# TPLE.net
KiCad netlist of a schematic drawn in EAGLE
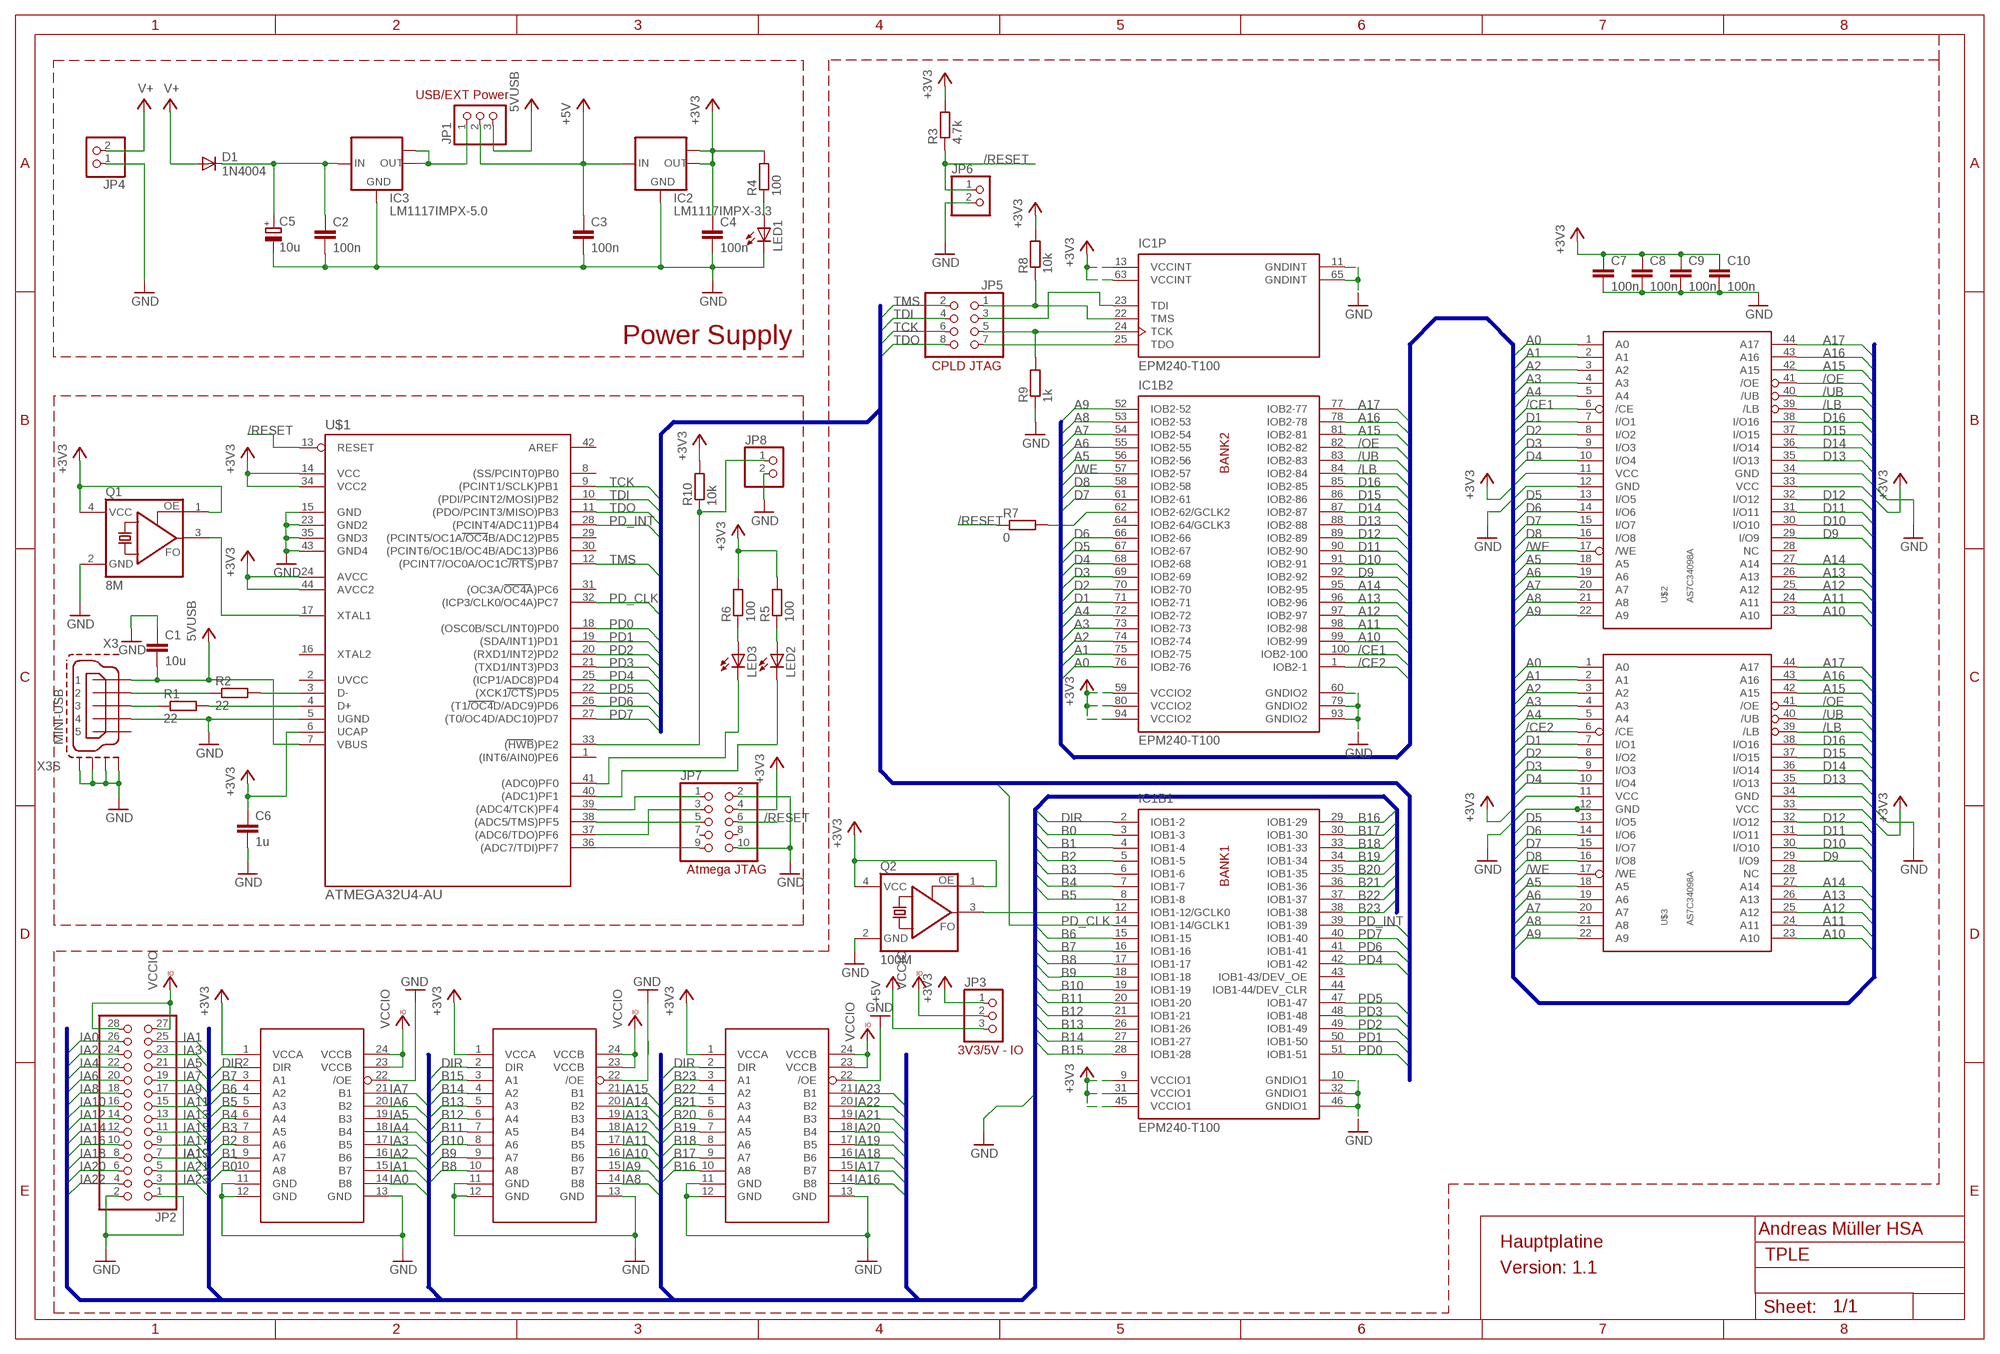
[diagram p0: schematic, sheet 1]

(export (version "E")
  (design (tool "Eeschema 10.0.6"))
  (components
    (comp (ref "C1")
      (value "10u")
      (footprint "eagle-import:C3216")
      (libsource (lib "eagle-import") (part "C-EUC3216"))
    )
    (comp (ref "C2")
      (value "100n")
      (footprint "eagle-import:C1206")
      (libsource (lib "eagle-import") (part "C-EUC1206"))
    )
    (comp (ref "C3")
      (value "100n")
      (footprint "eagle-import:C1206")
      (libsource (lib "eagle-import") (part "C-EUC1206"))
    )
    (comp (ref "C4")
      (value "100n")
      (footprint "eagle-import:C1206")
      (libsource (lib "eagle-import") (part "C-EUC1206"))
    )
    (comp (ref "C5")
      (value "10u")
      (footprint "eagle-import:E2-5")
      (libsource (lib "eagle-import") (part "CPOL-EUE2-5"))
    )
    (comp (ref "C6")
      (value "1u")
      (footprint "eagle-import:C0402")
      (libsource (lib "eagle-import") (part "C-EUC0402"))
    )
    (comp (ref "C7")
      (value "100n")
      (footprint "eagle-import:C0402")
      (libsource (lib "eagle-import") (part "C-EUC0402"))
    )
    (comp (ref "C8")
      (value "100n")
      (footprint "eagle-import:C0402")
      (libsource (lib "eagle-import") (part "C-EUC0402"))
    )
    (comp (ref "C9")
      (value "100n")
      (footprint "eagle-import:C0402")
      (libsource (lib "eagle-import") (part "C-EUC0402"))
    )
    (comp (ref "C10")
      (value "100n")
      (footprint "eagle-import:C0402")
      (libsource (lib "eagle-import") (part "C-EUC0402"))
    )
    (comp (ref "D1")
      (value "1N4004")
      (footprint "eagle-import:DO41-10")
      (libsource (lib "eagle-import") (part "1N4004"))
    )
    (comp (ref "IC1")
      (value "EPM240-T100")
      (footprint "eagle-import:TQFP100")
      (libsource (lib "eagle-import") (part "EPM240-T100"))
    )
    (comp (ref "IC2")
      (value "LM1117IMPX-3.3")
      (footprint "eagle-import:SOT223")
      (libsource (lib "eagle-import") (part "LM1117IMPX-3.3"))
    )
    (comp (ref "IC3")
      (value "LM1117IMPX-5.0")
      (footprint "eagle-import:SOT223")
      (libsource (lib "eagle-import") (part "LM1117IMPX-5.0"))
    )
    (comp (ref "JP1")
      (value "PINHD-1X3")
      (footprint "eagle-import:1X03")
      (libsource (lib "eagle-import") (part "PINHD-1X3"))
    )
    (comp (ref "JP2")
      (value "PINHD-2X14")
      (footprint "eagle-import:2X14")
      (libsource (lib "eagle-import") (part "PINHD-2X14"))
    )
    (comp (ref "JP3")
      (value "PINHD-1X3")
      (footprint "eagle-import:1X03")
      (libsource (lib "eagle-import") (part "PINHD-1X3"))
    )
    (comp (ref "JP4")
      (value "PINHD-1X2")
      (footprint "eagle-import:1X02")
      (libsource (lib "eagle-import") (part "PINHD-1X2"))
    )
    (comp (ref "JP5")
      (value "PINHD-2X4")
      (footprint "eagle-import:2X04")
      (libsource (lib "eagle-import") (part "PINHD-2X4"))
    )
    (comp (ref "JP6")
      (value "PINHD-1X2")
      (footprint "eagle-import:1X02")
      (libsource (lib "eagle-import") (part "PINHD-1X2"))
    )
    (comp (ref "JP7")
      (value "PINHD-2X5")
      (footprint "eagle-import:2X05")
      (libsource (lib "eagle-import") (part "PINHD-2X5"))
    )
    (comp (ref "JP8")
      (value "PINHD-1X2")
      (footprint "eagle-import:1X02")
      (libsource (lib "eagle-import") (part "PINHD-1X2"))
    )
    (comp (ref "LED1")
      (value "LEDSMT1206")
      (footprint "eagle-import:1206")
      (libsource (lib "eagle-import") (part "LEDSMT1206"))
    )
    (comp (ref "LED2")
      (value "LEDSMT1206")
      (footprint "eagle-import:1206")
      (libsource (lib "eagle-import") (part "LEDSMT1206"))
    )
    (comp (ref "LED3")
      (value "LEDSMT1206")
      (footprint "eagle-import:1206")
      (libsource (lib "eagle-import") (part "LEDSMT1206"))
    )
    (comp (ref "Q1")
      (value "8M")
      (footprint "eagle-import:ASF")
      (libsource (lib "eagle-import") (part "ASFL1"))
    )
    (comp (ref "Q2")
      (value "100M")
      (footprint "eagle-import:ASF")
      (libsource (lib "eagle-import") (part "ASFL1"))
    )
    (comp (ref "R1")
      (value "22")
      (footprint "eagle-import:M3216")
      (libsource (lib "eagle-import") (part "resistor_R-EU_M3216"))
    )
    (comp (ref "R2")
      (value "22")
      (footprint "eagle-import:M3216")
      (libsource (lib "eagle-import") (part "resistor_R-EU_M3216"))
    )
    (comp (ref "R3")
      (value "4.7k")
      (footprint "eagle-import:M3216")
      (libsource (lib "eagle-import") (part "resistor_R-EU_M3216"))
    )
    (comp (ref "R4")
      (value "100")
      (footprint "eagle-import:M3216")
      (libsource (lib "eagle-import") (part "resistor_R-EU_M3216"))
    )
    (comp (ref "R5")
      (value "100")
      (footprint "eagle-import:M3216")
      (libsource (lib "eagle-import") (part "resistor_R-EU_M3216"))
    )
    (comp (ref "R6")
      (value "100")
      (footprint "eagle-import:M3216")
      (libsource (lib "eagle-import") (part "resistor_R-EU_M3216"))
    )
    (comp (ref "R7")
      (value "0")
      (footprint "eagle-import:R0201")
      (libsource (lib "eagle-import") (part "R-EU_R0201"))
    )
    (comp (ref "R8")
      (value "10k")
      (footprint "eagle-import:M3216")
      (libsource (lib "eagle-import") (part "resistor_R-EU_M3216"))
    )
    (comp (ref "R9")
      (value "1k")
      (footprint "eagle-import:M3216")
      (libsource (lib "eagle-import") (part "resistor_R-EU_M3216"))
    )
    (comp (ref "R10")
      (value "10k")
      (footprint "eagle-import:R0402")
      (libsource (lib "eagle-import") (part "R-EU_R0402"))
    )
    (comp (ref "U$1")
      (value "ATMEGA32U4-AU")
      (footprint "eagle-import:TQFP44")
      (libsource (lib "eagle-import") (part "ATMEGA32U4-AU"))
    )
    (comp (ref "U$2")
      (value "AS7C34098A")
      (footprint "eagle-import:TSOP44-T2")
      (libsource (lib "eagle-import") (part "AS7C34098A"))
    )
    (comp (ref "U$3")
      (value "AS7C34098A")
      (footprint "eagle-import:TSOP44-T2")
      (libsource (lib "eagle-import") (part "AS7C34098A"))
    )
    (comp (ref "U$4")
      (value "SN74LVC8T245")
      (footprint "eagle-import:TVSOP24")
      (libsource (lib "eagle-import") (part "SN74LVC8T245"))
    )
    (comp (ref "U$5")
      (value "SN74LVC8T245")
      (footprint "eagle-import:TVSOP24")
      (libsource (lib "eagle-import") (part "SN74LVC8T245"))
    )
    (comp (ref "U$6")
      (value "SN74LVC8T245")
      (footprint "eagle-import:TVSOP24")
      (libsource (lib "eagle-import") (part "SN74LVC8T245"))
    )
    (comp (ref "X3")
      (value "MINI-USB")
      (footprint "eagle-import:UX60A-MB-5ST")
      (libsource (lib "eagle-import") (part "MINI-USB-SHIELD-UX60A-MB-5ST"))
    )
  )
  (nets
    (net (code "1") (name "+3V3") (class "Default")
      (node (ref "C10") (pin "1") (pinfunction "1_1") (pintype "passive"))
      (node (ref "C4") (pin "1") (pinfunction "1_1") (pintype "passive"))
      (node (ref "C6") (pin "1") (pinfunction "1_1") (pintype "passive"))
      (node (ref "C7") (pin "1") (pinfunction "1_1") (pintype "passive"))
      (node (ref "C8") (pin "1") (pinfunction "1_1") (pintype "passive"))
      (node (ref "C9") (pin "1") (pinfunction "1_1") (pintype "passive"))
      (node (ref "IC1") (pin "13") (pinfunction "VCCINT_13") (pintype "power_in"))
      (node (ref "IC1") (pin "31") (pinfunction "VCCIO1_31") (pintype "power_in"))
      (node (ref "IC1") (pin "45") (pinfunction "VCCIO1_45") (pintype "power_in"))
      (node (ref "IC1") (pin "59") (pinfunction "VCCIO2_59") (pintype "power_in"))
      (node (ref "IC1") (pin "63") (pinfunction "VCCINT_63") (pintype "power_in"))
      (node (ref "IC1") (pin "80") (pinfunction "VCCIO2_80") (pintype "power_in"))
      (node (ref "IC1") (pin "9") (pinfunction "VCCIO1_9") (pintype "power_in"))
      (node (ref "IC1") (pin "94") (pinfunction "VCCIO2_94") (pintype "power_in"))
      (node (ref "IC2") (pin "2") (pinfunction "OUT_2") (pintype "passive"))
      (node (ref "IC2") (pin "TAB") (pinfunction "OUT1_TAB") (pintype "passive"))
      (node (ref "JP3") (pin "1") (pinfunction "1_1") (pintype "passive"))
      (node (ref "JP7") (pin "4") (pinfunction "4_4") (pintype "passive"))
      (node (ref "Q1") (pin "1") (pinfunction "OE_1") (pintype "input"))
      (node (ref "Q1") (pin "4") (pinfunction "VCC_4") (pintype "power_in"))
      (node (ref "Q2") (pin "1") (pinfunction "OE_1") (pintype "input"))
      (node (ref "Q2") (pin "4") (pinfunction "VCC_4") (pintype "power_in"))
      (node (ref "R10") (pin "2") (pinfunction "2_2") (pintype "passive"))
      (node (ref "R3") (pin "2") (pinfunction "2_2") (pintype "passive"))
      (node (ref "R4") (pin "2") (pinfunction "2_2") (pintype "passive"))
      (node (ref "R5") (pin "2") (pinfunction "2_2") (pintype "passive"))
      (node (ref "R6") (pin "2") (pinfunction "2_2") (pintype "passive"))
      (node (ref "R8") (pin "2") (pinfunction "2_2") (pintype "passive"))
      (node (ref "U$1") (pin "14") (pinfunction "VCC_14") (pintype "bidirectional"))
      (node (ref "U$1") (pin "24") (pinfunction "AVCC_24") (pintype "bidirectional"))
      (node (ref "U$1") (pin "34") (pinfunction "VCC2_34") (pintype "bidirectional"))
      (node (ref "U$1") (pin "44") (pinfunction "AVCC2_44") (pintype "bidirectional"))
      (node (ref "U$1") (pin "6") (pinfunction "UCAP_6") (pintype "bidirectional"))
      (node (ref "U$2") (pin "11") (pinfunction "VCC_11") (pintype "power_in"))
      (node (ref "U$2") (pin "33") (pinfunction "VCC_33") (pintype "power_in"))
      (node (ref "U$3") (pin "11") (pinfunction "VCC_11") (pintype "power_in"))
      (node (ref "U$3") (pin "33") (pinfunction "VCC_33") (pintype "power_in"))
      (node (ref "U$4") (pin "1") (pinfunction "VCCA_1") (pintype "power_in"))
      (node (ref "U$5") (pin "1") (pinfunction "VCCA_1") (pintype "power_in"))
      (node (ref "U$6") (pin "1") (pinfunction "VCCA_1") (pintype "power_in"))
    )
    (net (code "2") (name "+5V") (class "Default")
      (node (ref "C3") (pin "1") (pinfunction "1_1") (pintype "passive"))
      (node (ref "IC2") (pin "3") (pinfunction "IN_3") (pintype "input"))
      (node (ref "JP1") (pin "2") (pinfunction "2_2") (pintype "passive"))
      (node (ref "JP3") (pin "3") (pinfunction "3_3") (pintype "passive"))
    )
    (net (code "3") (name "/A0") (class "Default")
      (node (ref "IC1") (pin "76") (pinfunction "IOB2-76_76") (pintype "bidirectional"))
      (node (ref "U$2") (pin "1") (pinfunction "A0_1") (pintype "input"))
      (node (ref "U$3") (pin "1") (pinfunction "A0_1") (pintype "input"))
    )
    (net (code "4") (name "/A1") (class "Default")
      (node (ref "IC1") (pin "75") (pinfunction "IOB2-75_75") (pintype "bidirectional"))
      (node (ref "U$2") (pin "2") (pinfunction "A1_2") (pintype "input"))
      (node (ref "U$3") (pin "2") (pinfunction "A1_2") (pintype "input"))
    )
    (net (code "5") (name "/A2") (class "Default")
      (node (ref "IC1") (pin "74") (pinfunction "IOB2-74_74") (pintype "bidirectional"))
      (node (ref "U$2") (pin "3") (pinfunction "A2_3") (pintype "input"))
      (node (ref "U$3") (pin "3") (pinfunction "A2_3") (pintype "input"))
    )
    (net (code "6") (name "/A3") (class "Default")
      (node (ref "IC1") (pin "73") (pinfunction "IOB2-73_73") (pintype "bidirectional"))
      (node (ref "U$2") (pin "4") (pinfunction "A3_4") (pintype "input"))
      (node (ref "U$3") (pin "4") (pinfunction "A3_4") (pintype "input"))
    )
    (net (code "7") (name "/A4") (class "Default")
      (node (ref "IC1") (pin "72") (pinfunction "IOB2-72_72") (pintype "bidirectional"))
      (node (ref "U$2") (pin "5") (pinfunction "A4_5") (pintype "input"))
      (node (ref "U$3") (pin "5") (pinfunction "A4_5") (pintype "input"))
    )
    (net (code "8") (name "/A5") (class "Default")
      (node (ref "IC1") (pin "56") (pinfunction "IOB2-56_56") (pintype "bidirectional"))
      (node (ref "U$2") (pin "18") (pinfunction "A5_18") (pintype "input"))
      (node (ref "U$3") (pin "18") (pinfunction "A5_18") (pintype "input"))
    )
    (net (code "9") (name "/A6") (class "Default")
      (node (ref "IC1") (pin "55") (pinfunction "IOB2-55_55") (pintype "bidirectional"))
      (node (ref "U$2") (pin "19") (pinfunction "A6_19") (pintype "input"))
      (node (ref "U$3") (pin "19") (pinfunction "A6_19") (pintype "input"))
    )
    (net (code "10") (name "/A7") (class "Default")
      (node (ref "IC1") (pin "54") (pinfunction "IOB2-54_54") (pintype "bidirectional"))
      (node (ref "U$2") (pin "20") (pinfunction "A7_20") (pintype "input"))
      (node (ref "U$3") (pin "20") (pinfunction "A7_20") (pintype "input"))
    )
    (net (code "11") (name "/A8") (class "Default")
      (node (ref "IC1") (pin "53") (pinfunction "IOB2-53_53") (pintype "bidirectional"))
      (node (ref "U$2") (pin "21") (pinfunction "A8_21") (pintype "input"))
      (node (ref "U$3") (pin "21") (pinfunction "A8_21") (pintype "input"))
    )
    (net (code "12") (name "/A9") (class "Default")
      (node (ref "IC1") (pin "52") (pinfunction "IOB2-52_52") (pintype "bidirectional"))
      (node (ref "U$2") (pin "22") (pinfunction "A9_22") (pintype "input"))
      (node (ref "U$3") (pin "22") (pinfunction "A9_22") (pintype "input"))
    )
    (net (code "13") (name "/A10") (class "Default")
      (node (ref "IC1") (pin "99") (pinfunction "IOB2-99_99") (pintype "bidirectional"))
      (node (ref "U$2") (pin "23") (pinfunction "A10_23") (pintype "input"))
      (node (ref "U$3") (pin "23") (pinfunction "A10_23") (pintype "input"))
    )
    (net (code "14") (name "/A11") (class "Default")
      (node (ref "IC1") (pin "98") (pinfunction "IOB2-98_98") (pintype "bidirectional"))
      (node (ref "U$2") (pin "24") (pinfunction "A11_24") (pintype "input"))
      (node (ref "U$3") (pin "24") (pinfunction "A11_24") (pintype "input"))
    )
    (net (code "15") (name "/A12") (class "Default")
      (node (ref "IC1") (pin "97") (pinfunction "IOB2-97_97") (pintype "bidirectional"))
      (node (ref "U$2") (pin "25") (pinfunction "A12_25") (pintype "input"))
      (node (ref "U$3") (pin "25") (pinfunction "A12_25") (pintype "input"))
    )
    (net (code "16") (name "/A13") (class "Default")
      (node (ref "IC1") (pin "96") (pinfunction "IOB2-96_96") (pintype "bidirectional"))
      (node (ref "U$2") (pin "26") (pinfunction "A13_26") (pintype "input"))
      (node (ref "U$3") (pin "26") (pinfunction "A13_26") (pintype "input"))
    )
    (net (code "17") (name "/A14") (class "Default")
      (node (ref "IC1") (pin "95") (pinfunction "IOB2-95_95") (pintype "bidirectional"))
      (node (ref "U$2") (pin "27") (pinfunction "A14_27") (pintype "input"))
      (node (ref "U$3") (pin "27") (pinfunction "A14_27") (pintype "input"))
    )
    (net (code "18") (name "/A15") (class "Default")
      (node (ref "IC1") (pin "81") (pinfunction "IOB2-81_81") (pintype "bidirectional"))
      (node (ref "U$2") (pin "42") (pinfunction "A15_42") (pintype "input"))
      (node (ref "U$3") (pin "42") (pinfunction "A15_42") (pintype "input"))
    )
    (net (code "19") (name "/A16") (class "Default")
      (node (ref "IC1") (pin "78") (pinfunction "IOB2-78_78") (pintype "bidirectional"))
      (node (ref "U$2") (pin "43") (pinfunction "A16_43") (pintype "input"))
      (node (ref "U$3") (pin "43") (pinfunction "A16_43") (pintype "input"))
    )
    (net (code "20") (name "/A17") (class "Default")
      (node (ref "IC1") (pin "77") (pinfunction "IOB2-77_77") (pintype "bidirectional"))
      (node (ref "U$2") (pin "44") (pinfunction "A17_44") (pintype "input"))
      (node (ref "U$3") (pin "44") (pinfunction "A17_44") (pintype "input"))
    )
    (net (code "21") (name "/B0") (class "Default")
      (node (ref "IC1") (pin "3") (pinfunction "IOB1-3_3") (pintype "bidirectional"))
      (node (ref "U$4") (pin "10") (pinfunction "A8_10") (pintype "bidirectional"))
    )
    (net (code "22") (name "/B1") (class "Default")
      (node (ref "IC1") (pin "4") (pinfunction "IOB1-4_4") (pintype "bidirectional"))
      (node (ref "U$4") (pin "9") (pinfunction "A7_9") (pintype "bidirectional"))
    )
    (net (code "23") (name "/B2") (class "Default")
      (node (ref "IC1") (pin "5") (pinfunction "IOB1-5_5") (pintype "bidirectional"))
      (node (ref "U$4") (pin "8") (pinfunction "A6_8") (pintype "bidirectional"))
    )
    (net (code "24") (name "/B3") (class "Default")
      (node (ref "IC1") (pin "6") (pinfunction "IOB1-6_6") (pintype "bidirectional"))
      (node (ref "U$4") (pin "7") (pinfunction "A5_7") (pintype "bidirectional"))
    )
    (net (code "25") (name "/B4") (class "Default")
      (node (ref "IC1") (pin "7") (pinfunction "IOB1-7_7") (pintype "bidirectional"))
      (node (ref "U$4") (pin "6") (pinfunction "A4_6") (pintype "bidirectional"))
    )
    (net (code "26") (name "/B5") (class "Default")
      (node (ref "IC1") (pin "8") (pinfunction "IOB1-8_8") (pintype "bidirectional"))
      (node (ref "U$4") (pin "5") (pinfunction "A3_5") (pintype "bidirectional"))
    )
    (net (code "27") (name "/B6") (class "Default")
      (node (ref "IC1") (pin "15") (pinfunction "IOB1-15_15") (pintype "bidirectional"))
      (node (ref "U$4") (pin "4") (pinfunction "A2_4") (pintype "bidirectional"))
    )
    (net (code "28") (name "/B7") (class "Default")
      (node (ref "IC1") (pin "16") (pinfunction "IOB1-16_16") (pintype "bidirectional"))
      (node (ref "U$4") (pin "3") (pinfunction "A1_3") (pintype "bidirectional"))
    )
    (net (code "29") (name "/B8") (class "Default")
      (node (ref "IC1") (pin "17") (pinfunction "IOB1-17_17") (pintype "bidirectional"))
      (node (ref "U$5") (pin "10") (pinfunction "A8_10") (pintype "bidirectional"))
    )
    (net (code "30") (name "/B9") (class "Default")
      (node (ref "IC1") (pin "18") (pinfunction "IOB1-18_18") (pintype "bidirectional"))
      (node (ref "U$5") (pin "9") (pinfunction "A7_9") (pintype "bidirectional"))
    )
    (net (code "31") (name "/B10") (class "Default")
      (node (ref "IC1") (pin "19") (pinfunction "IOB1-19_19") (pintype "bidirectional"))
      (node (ref "U$5") (pin "8") (pinfunction "A6_8") (pintype "bidirectional"))
    )
    (net (code "32") (name "/B11") (class "Default")
      (node (ref "IC1") (pin "20") (pinfunction "IOB1-20_20") (pintype "bidirectional"))
      (node (ref "U$5") (pin "7") (pinfunction "A5_7") (pintype "bidirectional"))
    )
    (net (code "33") (name "/B12") (class "Default")
      (node (ref "IC1") (pin "21") (pinfunction "IOB1-21_21") (pintype "bidirectional"))
      (node (ref "U$5") (pin "6") (pinfunction "A4_6") (pintype "bidirectional"))
    )
    (net (code "34") (name "/B13") (class "Default")
      (node (ref "IC1") (pin "26") (pinfunction "IOB1-26_26") (pintype "bidirectional"))
      (node (ref "U$5") (pin "5") (pinfunction "A3_5") (pintype "bidirectional"))
    )
    (net (code "35") (name "/B14") (class "Default")
      (node (ref "IC1") (pin "27") (pinfunction "IOB1-27_27") (pintype "bidirectional"))
      (node (ref "U$5") (pin "4") (pinfunction "A2_4") (pintype "bidirectional"))
    )
    (net (code "36") (name "/B15") (class "Default")
      (node (ref "IC1") (pin "28") (pinfunction "IOB1-28_28") (pintype "bidirectional"))
      (node (ref "U$5") (pin "3") (pinfunction "A1_3") (pintype "bidirectional"))
    )
    (net (code "37") (name "/B16") (class "Default")
      (node (ref "IC1") (pin "29") (pinfunction "IOB1-29_29") (pintype "bidirectional"))
      (node (ref "U$6") (pin "10") (pinfunction "A8_10") (pintype "bidirectional"))
    )
    (net (code "38") (name "/B17") (class "Default")
      (node (ref "IC1") (pin "30") (pinfunction "IOB1-30_30") (pintype "bidirectional"))
      (node (ref "U$6") (pin "9") (pinfunction "A7_9") (pintype "bidirectional"))
    )
    (net (code "39") (name "/B18") (class "Default")
      (node (ref "IC1") (pin "33") (pinfunction "IOB1-33_33") (pintype "bidirectional"))
      (node (ref "U$6") (pin "8") (pinfunction "A6_8") (pintype "bidirectional"))
    )
    (net (code "40") (name "/B19") (class "Default")
      (node (ref "IC1") (pin "34") (pinfunction "IOB1-34_34") (pintype "bidirectional"))
      (node (ref "U$6") (pin "7") (pinfunction "A5_7") (pintype "bidirectional"))
    )
    (net (code "41") (name "/B20") (class "Default")
      (node (ref "IC1") (pin "35") (pinfunction "IOB1-35_35") (pintype "bidirectional"))
      (node (ref "U$6") (pin "6") (pinfunction "A4_6") (pintype "bidirectional"))
    )
    (net (code "42") (name "/B21") (class "Default")
      (node (ref "IC1") (pin "36") (pinfunction "IOB1-36_36") (pintype "bidirectional"))
      (node (ref "U$6") (pin "5") (pinfunction "A3_5") (pintype "bidirectional"))
    )
    (net (code "43") (name "/B22") (class "Default")
      (node (ref "IC1") (pin "37") (pinfunction "IOB1-37_37") (pintype "bidirectional"))
      (node (ref "U$6") (pin "4") (pinfunction "A2_4") (pintype "bidirectional"))
    )
    (net (code "44") (name "/B23") (class "Default")
      (node (ref "IC1") (pin "38") (pinfunction "IOB1-38_38") (pintype "bidirectional"))
      (node (ref "U$6") (pin "3") (pinfunction "A1_3") (pintype "bidirectional"))
    )
    (net (code "45") (name "/D1") (class "Default")
      (node (ref "IC1") (pin "71") (pinfunction "IOB2-71_71") (pintype "bidirectional"))
      (node (ref "U$2") (pin "7") (pinfunction "I/O1_7") (pintype "bidirectional"))
      (node (ref "U$3") (pin "7") (pinfunction "I/O1_7") (pintype "bidirectional"))
    )
    (net (code "46") (name "/D2") (class "Default")
      (node (ref "IC1") (pin "70") (pinfunction "IOB2-70_70") (pintype "bidirectional"))
      (node (ref "U$2") (pin "8") (pinfunction "I/O2_8") (pintype "bidirectional"))
      (node (ref "U$3") (pin "8") (pinfunction "I/O2_8") (pintype "bidirectional"))
    )
    (net (code "47") (name "/D3") (class "Default")
      (node (ref "IC1") (pin "69") (pinfunction "IOB2-69_69") (pintype "bidirectional"))
      (node (ref "U$2") (pin "9") (pinfunction "I/O3_9") (pintype "bidirectional"))
      (node (ref "U$3") (pin "9") (pinfunction "I/O3_9") (pintype "bidirectional"))
    )
    (net (code "48") (name "/D4") (class "Default")
      (node (ref "IC1") (pin "68") (pinfunction "IOB2-68_68") (pintype "bidirectional"))
      (node (ref "U$2") (pin "10") (pinfunction "I/O4_10") (pintype "bidirectional"))
      (node (ref "U$3") (pin "10") (pinfunction "I/O4_10") (pintype "bidirectional"))
    )
    (net (code "49") (name "/D5") (class "Default")
      (node (ref "IC1") (pin "67") (pinfunction "IOB2-67_67") (pintype "bidirectional"))
      (node (ref "U$2") (pin "13") (pinfunction "I/O5_13") (pintype "bidirectional"))
      (node (ref "U$3") (pin "13") (pinfunction "I/O5_13") (pintype "bidirectional"))
    )
    (net (code "50") (name "/D6") (class "Default")
      (node (ref "IC1") (pin "66") (pinfunction "IOB2-66_66") (pintype "bidirectional"))
      (node (ref "U$2") (pin "14") (pinfunction "I/O6_14") (pintype "bidirectional"))
      (node (ref "U$3") (pin "14") (pinfunction "I/O6_14") (pintype "bidirectional"))
    )
    (net (code "51") (name "/D7") (class "Default")
      (node (ref "IC1") (pin "61") (pinfunction "IOB2-61_61") (pintype "bidirectional"))
      (node (ref "U$2") (pin "15") (pinfunction "I/O7_15") (pintype "bidirectional"))
      (node (ref "U$3") (pin "15") (pinfunction "I/O7_15") (pintype "bidirectional"))
    )
    (net (code "52") (name "/D8") (class "Default")
      (node (ref "IC1") (pin "58") (pinfunction "IOB2-58_58") (pintype "bidirectional"))
      (node (ref "U$2") (pin "16") (pinfunction "I/O8_16") (pintype "bidirectional"))
      (node (ref "U$3") (pin "16") (pinfunction "I/O8_16") (pintype "bidirectional"))
    )
    (net (code "53") (name "/D9") (class "Default")
      (node (ref "IC1") (pin "92") (pinfunction "IOB2-92_92") (pintype "bidirectional"))
      (node (ref "U$2") (pin "29") (pinfunction "I/O9_29") (pintype "bidirectional"))
      (node (ref "U$3") (pin "29") (pinfunction "I/O9_29") (pintype "bidirectional"))
    )
    (net (code "54") (name "/D10") (class "Default")
      (node (ref "IC1") (pin "91") (pinfunction "IOB2-91_91") (pintype "bidirectional"))
      (node (ref "U$2") (pin "30") (pinfunction "I/O10_30") (pintype "bidirectional"))
      (node (ref "U$3") (pin "30") (pinfunction "I/O10_30") (pintype "bidirectional"))
    )
    (net (code "55") (name "/D11") (class "Default")
      (node (ref "IC1") (pin "90") (pinfunction "IOB2-90_90") (pintype "bidirectional"))
      (node (ref "U$2") (pin "31") (pinfunction "I/O11_31") (pintype "bidirectional"))
      (node (ref "U$3") (pin "31") (pinfunction "I/O11_31") (pintype "bidirectional"))
    )
    (net (code "56") (name "/D12") (class "Default")
      (node (ref "IC1") (pin "89") (pinfunction "IOB2-89_89") (pintype "bidirectional"))
      (node (ref "U$2") (pin "32") (pinfunction "I/O12_32") (pintype "bidirectional"))
      (node (ref "U$3") (pin "32") (pinfunction "I/O12_32") (pintype "bidirectional"))
    )
    (net (code "57") (name "/D13") (class "Default")
      (node (ref "IC1") (pin "88") (pinfunction "IOB2-88_88") (pintype "bidirectional"))
      (node (ref "U$2") (pin "35") (pinfunction "I/O13_35") (pintype "bidirectional"))
      (node (ref "U$3") (pin "35") (pinfunction "I/O13_35") (pintype "bidirectional"))
    )
    (net (code "58") (name "/D14") (class "Default")
      (node (ref "IC1") (pin "87") (pinfunction "IOB2-87_87") (pintype "bidirectional"))
      (node (ref "U$2") (pin "36") (pinfunction "I/O14_36") (pintype "bidirectional"))
      (node (ref "U$3") (pin "36") (pinfunction "I/O14_36") (pintype "bidirectional"))
    )
    (net (code "59") (name "/D15") (class "Default")
      (node (ref "IC1") (pin "86") (pinfunction "IOB2-86_86") (pintype "bidirectional"))
      (node (ref "U$2") (pin "37") (pinfunction "I/O15_37") (pintype "bidirectional"))
      (node (ref "U$3") (pin "37") (pinfunction "I/O15_37") (pintype "bidirectional"))
    )
    (net (code "60") (name "/D16") (class "Default")
      (node (ref "IC1") (pin "85") (pinfunction "IOB2-85_85") (pintype "bidirectional"))
      (node (ref "U$2") (pin "38") (pinfunction "I/O16_38") (pintype "bidirectional"))
      (node (ref "U$3") (pin "38") (pinfunction "I/O16_38") (pintype "bidirectional"))
    )
    (net (code "61") (name "/DIR") (class "Default")
      (node (ref "IC1") (pin "2") (pinfunction "IOB1-2_2") (pintype "bidirectional"))
      (node (ref "U$4") (pin "2") (pinfunction "DIR_2") (pintype "input"))
      (node (ref "U$5") (pin "2") (pinfunction "DIR_2") (pintype "input"))
      (node (ref "U$6") (pin "2") (pinfunction "DIR_2") (pintype "input"))
    )
    (net (code "62") (name "/IA0") (class "Default")
      (node (ref "JP2") (pin "26") (pinfunction "26_26") (pintype "passive"))
      (node (ref "U$4") (pin "14") (pinfunction "B8_14") (pintype "bidirectional"))
    )
    (net (code "63") (name "/IA1") (class "Default")
      (node (ref "JP2") (pin "25") (pinfunction "25_25") (pintype "passive"))
      (node (ref "U$4") (pin "15") (pinfunction "B7_15") (pintype "bidirectional"))
    )
    (net (code "64") (name "/IA2") (class "Default")
      (node (ref "JP2") (pin "24") (pinfunction "24_24") (pintype "passive"))
      (node (ref "U$4") (pin "16") (pinfunction "B6_16") (pintype "bidirectional"))
    )
    (net (code "65") (name "/IA3") (class "Default")
      (node (ref "JP2") (pin "23") (pinfunction "23_23") (pintype "passive"))
      (node (ref "U$4") (pin "17") (pinfunction "B5_17") (pintype "bidirectional"))
    )
    (net (code "66") (name "/IA4") (class "Default")
      (node (ref "JP2") (pin "22") (pinfunction "22_22") (pintype "passive"))
      (node (ref "U$4") (pin "18") (pinfunction "B4_18") (pintype "bidirectional"))
    )
    (net (code "67") (name "/IA5") (class "Default")
      (node (ref "JP2") (pin "21") (pinfunction "21_21") (pintype "passive"))
      (node (ref "U$4") (pin "19") (pinfunction "B3_19") (pintype "bidirectional"))
    )
    (net (code "68") (name "/IA6") (class "Default")
      (node (ref "JP2") (pin "20") (pinfunction "20_20") (pintype "passive"))
      (node (ref "U$4") (pin "20") (pinfunction "B2_20") (pintype "bidirectional"))
    )
    (net (code "69") (name "/IA7") (class "Default")
      (node (ref "JP2") (pin "19") (pinfunction "19_19") (pintype "passive"))
      (node (ref "U$4") (pin "21") (pinfunction "B1_21") (pintype "bidirectional"))
    )
    (net (code "70") (name "/IA8") (class "Default")
      (node (ref "JP2") (pin "18") (pinfunction "18_18") (pintype "passive"))
      (node (ref "U$5") (pin "14") (pinfunction "B8_14") (pintype "bidirectional"))
    )
    (net (code "71") (name "/IA9") (class "Default")
      (node (ref "JP2") (pin "17") (pinfunction "17_17") (pintype "passive"))
      (node (ref "U$5") (pin "15") (pinfunction "B7_15") (pintype "bidirectional"))
    )
    (net (code "72") (name "/IA10") (class "Default")
      (node (ref "JP2") (pin "16") (pinfunction "16_16") (pintype "passive"))
      (node (ref "U$5") (pin "16") (pinfunction "B6_16") (pintype "bidirectional"))
    )
    (net (code "73") (name "/IA11") (class "Default")
      (node (ref "JP2") (pin "15") (pinfunction "15_15") (pintype "passive"))
      (node (ref "U$5") (pin "17") (pinfunction "B5_17") (pintype "bidirectional"))
    )
    (net (code "74") (name "/IA12") (class "Default")
      (node (ref "JP2") (pin "14") (pinfunction "14_14") (pintype "passive"))
      (node (ref "U$5") (pin "18") (pinfunction "B4_18") (pintype "bidirectional"))
    )
    (net (code "75") (name "/IA13") (class "Default")
      (node (ref "JP2") (pin "13") (pinfunction "13_13") (pintype "passive"))
      (node (ref "U$5") (pin "19") (pinfunction "B3_19") (pintype "bidirectional"))
    )
    (net (code "76") (name "/IA14") (class "Default")
      (node (ref "JP2") (pin "12") (pinfunction "12_12") (pintype "passive"))
      (node (ref "U$5") (pin "20") (pinfunction "B2_20") (pintype "bidirectional"))
    )
    (net (code "77") (name "/IA15") (class "Default")
      (node (ref "JP2") (pin "11") (pinfunction "11_11") (pintype "passive"))
      (node (ref "U$5") (pin "21") (pinfunction "B1_21") (pintype "bidirectional"))
    )
    (net (code "78") (name "/IA16") (class "Default")
      (node (ref "JP2") (pin "10") (pinfunction "10_10") (pintype "passive"))
      (node (ref "U$6") (pin "14") (pinfunction "B8_14") (pintype "bidirectional"))
    )
    (net (code "79") (name "/IA17") (class "Default")
      (node (ref "JP2") (pin "9") (pinfunction "9_9") (pintype "passive"))
      (node (ref "U$6") (pin "15") (pinfunction "B7_15") (pintype "bidirectional"))
    )
    (net (code "80") (name "/IA18") (class "Default")
      (node (ref "JP2") (pin "8") (pinfunction "8_8") (pintype "passive"))
      (node (ref "U$6") (pin "16") (pinfunction "B6_16") (pintype "bidirectional"))
    )
    (net (code "81") (name "/IA19") (class "Default")
      (node (ref "JP2") (pin "7") (pinfunction "7_7") (pintype "passive"))
      (node (ref "U$6") (pin "17") (pinfunction "B5_17") (pintype "bidirectional"))
    )
    (net (code "82") (name "/IA20") (class "Default")
      (node (ref "JP2") (pin "6") (pinfunction "6_6") (pintype "passive"))
      (node (ref "U$6") (pin "18") (pinfunction "B4_18") (pintype "bidirectional"))
    )
    (net (code "83") (name "/IA21") (class "Default")
      (node (ref "JP2") (pin "5") (pinfunction "5_5") (pintype "passive"))
      (node (ref "U$6") (pin "19") (pinfunction "B3_19") (pintype "bidirectional"))
    )
    (net (code "84") (name "/IA22") (class "Default")
      (node (ref "JP2") (pin "4") (pinfunction "4_4") (pintype "passive"))
      (node (ref "U$6") (pin "20") (pinfunction "B2_20") (pintype "bidirectional"))
    )
    (net (code "85") (name "/IA23") (class "Default")
      (node (ref "JP2") (pin "3") (pinfunction "3_3") (pintype "passive"))
      (node (ref "U$6") (pin "21") (pinfunction "B1_21") (pintype "bidirectional"))
    )
    (net (code "86") (name "/PD0") (class "Default")
      (node (ref "IC1") (pin "51") (pinfunction "IOB1-51_51") (pintype "bidirectional"))
      (node (ref "U$1") (pin "18") (pinfunction "(OSC0B/SCL/INT0)PD0_18") (pintype "bidirectional"))
    )
    (net (code "87") (name "/PD1") (class "Default")
      (node (ref "IC1") (pin "50") (pinfunction "IOB1-50_50") (pintype "bidirectional"))
      (node (ref "U$1") (pin "19") (pinfunction "(SDA/INT1)PD1_19") (pintype "bidirectional"))
    )
    (net (code "88") (name "/PD2") (class "Default")
      (node (ref "IC1") (pin "49") (pinfunction "IOB1-49_49") (pintype "bidirectional"))
      (node (ref "U$1") (pin "20") (pinfunction "(RXD1/INT2)PD2_20") (pintype "bidirectional"))
    )
    (net (code "89") (name "/PD3") (class "Default")
      (node (ref "IC1") (pin "48") (pinfunction "IOB1-48_48") (pintype "bidirectional"))
      (node (ref "U$1") (pin "21") (pinfunction "(TXD1/INT3)PD3_21") (pintype "bidirectional"))
    )
    (net (code "90") (name "/PD4") (class "Default")
      (node (ref "IC1") (pin "42") (pinfunction "IOB1-42_42") (pintype "bidirectional"))
      (node (ref "U$1") (pin "25") (pinfunction "(ICP1/ADC8)PD4_25") (pintype "bidirectional"))
    )
    (net (code "91") (name "/PD5") (class "Default")
      (node (ref "IC1") (pin "47") (pinfunction "IOB1-47_47") (pintype "bidirectional"))
      (node (ref "U$1") (pin "22") (pinfunction "(XCK1/CTS)PD5_22") (pintype "bidirectional"))
    )
    (net (code "92") (name "/PD6") (class "Default")
      (node (ref "IC1") (pin "41") (pinfunction "IOB1-41_41") (pintype "bidirectional"))
      (node (ref "U$1") (pin "26") (pinfunction "(T1/OC4D/ADC9)PD6_26") (pintype "bidirectional"))
    )
    (net (code "93") (name "/PD7") (class "Default")
      (node (ref "IC1") (pin "40") (pinfunction "IOB1-40_40") (pintype "bidirectional"))
      (node (ref "U$1") (pin "27") (pinfunction "(T0/OC4D/ADC10)PD7_27") (pintype "bidirectional"))
    )
    (net (code "94") (name "/PD_CLK") (class "Default")
      (node (ref "IC1") (pin "14") (pinfunction "IOB1-14/GCLK1_14") (pintype "bidirectional"))
      (node (ref "U$1") (pin "32") (pinfunction "(ICP3/CLK0/OC4A)PC7_32") (pintype "bidirectional"))
    )
    (net (code "95") (name "/PD_INT") (class "Default")
      (node (ref "IC1") (pin "39") (pinfunction "IOB1-39_39") (pintype "bidirectional"))
      (node (ref "U$1") (pin "28") (pinfunction "(PCINT4/ADC11)PB4_28") (pintype "bidirectional"))
    )
    (net (code "96") (name "/TCK") (class "Default")
      (node (ref "JP5") (pin "6") (pinfunction "6_6") (pintype "passive"))
      (node (ref "U$1") (pin "9") (pinfunction "(PCINT1/SCLK)PB1_9") (pintype "bidirectional"))
    )
    (net (code "97") (name "/TDI") (class "Default")
      (node (ref "JP5") (pin "4") (pinfunction "4_4") (pintype "passive"))
      (node (ref "U$1") (pin "10") (pinfunction "(PDI/PCINT2/MOSI)PB2_10") (pintype "bidirectional"))
    )
    (net (code "98") (name "/TDO") (class "Default")
      (node (ref "JP5") (pin "8") (pinfunction "8_8") (pintype "passive"))
      (node (ref "U$1") (pin "11") (pinfunction "(PDO/PCINT3/MISO)PB3_11") (pintype "bidirectional"))
    )
    (net (code "99") (name "/TMS") (class "Default")
      (node (ref "JP5") (pin "2") (pinfunction "2_2") (pintype "passive"))
      (node (ref "U$1") (pin "12") (pinfunction "(PCINT7/OC0A/OC1C/RTS)PB7_12") (pintype "bidirectional"))
    )
    (net (code "100") (name "/{slash}CE1") (class "Default")
      (node (ref "IC1") (pin "100") (pinfunction "IOB2-100_100") (pintype "bidirectional"))
      (node (ref "U$2") (pin "6") (pinfunction "/CE_6") (pintype "input"))
    )
    (net (code "101") (name "/{slash}CE2") (class "Default")
      (node (ref "IC1") (pin "1") (pinfunction "IOB2-1_1") (pintype "bidirectional"))
      (node (ref "U$3") (pin "6") (pinfunction "/CE_6") (pintype "input"))
    )
    (net (code "102") (name "/{slash}LB") (class "Default")
      (node (ref "IC1") (pin "84") (pinfunction "IOB2-84_84") (pintype "bidirectional"))
      (node (ref "U$2") (pin "39") (pinfunction "/LB_39") (pintype "input"))
      (node (ref "U$3") (pin "39") (pinfunction "/LB_39") (pintype "input"))
    )
    (net (code "103") (name "/{slash}OE") (class "Default")
      (node (ref "IC1") (pin "82") (pinfunction "IOB2-82_82") (pintype "bidirectional"))
      (node (ref "U$2") (pin "41") (pinfunction "/OE_41") (pintype "input"))
      (node (ref "U$3") (pin "41") (pinfunction "/OE_41") (pintype "input"))
    )
    (net (code "104") (name "/{slash}RESET") (class "Default")
      (node (ref "JP6") (pin "1") (pinfunction "1_1") (pintype "passive"))
      (node (ref "JP7") (pin "6") (pinfunction "6_6") (pintype "passive"))
      (node (ref "R3") (pin "1") (pinfunction "1_1") (pintype "passive"))
      (node (ref "R7") (pin "1") (pinfunction "1_1") (pintype "passive"))
      (node (ref "U$1") (pin "13") (pinfunction "RESET_13") (pintype "bidirectional"))
    )
    (net (code "105") (name "/{slash}UB") (class "Default")
      (node (ref "IC1") (pin "83") (pinfunction "IOB2-83_83") (pintype "bidirectional"))
      (node (ref "U$2") (pin "40") (pinfunction "/UB_40") (pintype "input"))
      (node (ref "U$3") (pin "40") (pinfunction "/UB_40") (pintype "input"))
    )
    (net (code "106") (name "/{slash}WE") (class "Default")
      (node (ref "IC1") (pin "57") (pinfunction "IOB2-57_57") (pintype "bidirectional"))
      (node (ref "U$2") (pin "17") (pinfunction "/WE_17") (pintype "input"))
      (node (ref "U$3") (pin "17") (pinfunction "/WE_17") (pintype "input"))
    )
    (net (code "107") (name "5VUSB") (class "Default")
      (node (ref "C1") (pin "2") (pinfunction "2_2") (pintype "passive"))
      (node (ref "JP1") (pin "3") (pinfunction "3_3") (pintype "passive"))
      (node (ref "U$1") (pin "7") (pinfunction "VBUS_7") (pintype "bidirectional"))
      (node (ref "X3") (pin "1") (pinfunction "1_1") (pintype "input"))
    )
    (net (code "108") (name "GND") (class "Default")
      (node (ref "C1") (pin "1") (pinfunction "1_1") (pintype "passive"))
      (node (ref "C10") (pin "2") (pinfunction "2_2") (pintype "passive"))
      (node (ref "C2") (pin "2") (pinfunction "2_2") (pintype "passive"))
      (node (ref "C3") (pin "2") (pinfunction "2_2") (pintype "passive"))
      (node (ref "C4") (pin "2") (pinfunction "2_2") (pintype "passive"))
      (node (ref "C5") (pin "-") (pinfunction "-_-") (pintype "passive"))
      (node (ref "C6") (pin "2") (pinfunction "2_2") (pintype "passive"))
      (node (ref "C7") (pin "2") (pinfunction "2_2") (pintype "passive"))
      (node (ref "C8") (pin "2") (pinfunction "2_2") (pintype "passive"))
      (node (ref "C9") (pin "2") (pinfunction "2_2") (pintype "passive"))
      (node (ref "IC1") (pin "10") (pinfunction "GNDIO1_10") (pintype "power_in"))
      (node (ref "IC1") (pin "11") (pinfunction "GNDINT_11") (pintype "power_in"))
      (node (ref "IC1") (pin "32") (pinfunction "GNDIO1_32") (pintype "power_in"))
      (node (ref "IC1") (pin "46") (pinfunction "GNDIO1_46") (pintype "power_in"))
      (node (ref "IC1") (pin "60") (pinfunction "GNDIO2_60") (pintype "power_in"))
      (node (ref "IC1") (pin "65") (pinfunction "GNDINT_65") (pintype "power_in"))
      (node (ref "IC1") (pin "79") (pinfunction "GNDIO2_79") (pintype "power_in"))
      (node (ref "IC1") (pin "93") (pinfunction "GNDIO2_93") (pintype "power_in"))
      (node (ref "IC2") (pin "1") (pinfunction "GND_1") (pintype "input"))
      (node (ref "IC3") (pin "1") (pinfunction "GND_1") (pintype "input"))
      (node (ref "JP2") (pin "1") (pinfunction "1_1") (pintype "passive"))
      (node (ref "JP2") (pin "2") (pinfunction "2_2") (pintype "passive"))
      (node (ref "JP4") (pin "1") (pinfunction "1_1") (pintype "passive"))
      (node (ref "JP6") (pin "2") (pinfunction "2_2") (pintype "passive"))
      (node (ref "JP7") (pin "10") (pinfunction "10_10") (pintype "passive"))
      (node (ref "JP7") (pin "2") (pinfunction "2_2") (pintype "passive"))
      (node (ref "JP8") (pin "2") (pinfunction "2_2") (pintype "passive"))
      (node (ref "LED1") (pin "C") (pinfunction "C_C") (pintype "passive"))
      (node (ref "Q1") (pin "2") (pinfunction "GND_2") (pintype "power_in"))
      (node (ref "Q2") (pin "2") (pinfunction "GND_2") (pintype "power_in"))
      (node (ref "R9") (pin "1") (pinfunction "1_1") (pintype "passive"))
      (node (ref "U$1") (pin "15") (pinfunction "GND_15") (pintype "bidirectional"))
      (node (ref "U$1") (pin "23") (pinfunction "GND2_23") (pintype "bidirectional"))
      (node (ref "U$1") (pin "35") (pinfunction "GND3_35") (pintype "bidirectional"))
      (node (ref "U$1") (pin "43") (pinfunction "GND4_43") (pintype "bidirectional"))
      (node (ref "U$1") (pin "5") (pinfunction "UGND_5") (pintype "bidirectional"))
      (node (ref "U$2") (pin "12") (pinfunction "GND_12") (pintype "power_in"))
      (node (ref "U$2") (pin "34") (pinfunction "GND_34") (pintype "power_in"))
      (node (ref "U$3") (pin "12") (pinfunction "GND_12") (pintype "power_in"))
      (node (ref "U$3") (pin "34") (pinfunction "GND_34") (pintype "power_in"))
      (node (ref "U$4") (pin "11") (pinfunction "GND_11") (pintype "power_in"))
      (node (ref "U$4") (pin "12") (pinfunction "GND_12") (pintype "power_in"))
      (node (ref "U$4") (pin "13") (pinfunction "GND_13") (pintype "power_in"))
      (node (ref "U$4") (pin "22") (pinfunction "/OE_22") (pintype "input"))
      (node (ref "U$5") (pin "11") (pinfunction "GND_11") (pintype "power_in"))
      (node (ref "U$5") (pin "12") (pinfunction "GND_12") (pintype "power_in"))
      (node (ref "U$5") (pin "13") (pinfunction "GND_13") (pintype "power_in"))
      (node (ref "U$5") (pin "22") (pinfunction "/OE_22") (pintype "input"))
      (node (ref "U$6") (pin "11") (pinfunction "GND_11") (pintype "power_in"))
      (node (ref "U$6") (pin "12") (pinfunction "GND_12") (pintype "power_in"))
      (node (ref "U$6") (pin "13") (pinfunction "GND_13") (pintype "power_in"))
      (node (ref "U$6") (pin "22") (pinfunction "/OE_22") (pintype "input"))
      (node (ref "X3") (pin "4") (pinfunction "4_4") (pintype "input"))
      (node (ref "X3") (pin "M1") (pinfunction "S1_M1") (pintype "passive"))
      (node (ref "X3") (pin "M2") (pinfunction "S2_M2") (pintype "passive"))
      (node (ref "X3") (pin "M3") (pinfunction "S3_M3") (pintype "passive"))
      (node (ref "X3") (pin "M4") (pinfunction "S4_M4") (pintype "passive"))
    )
    (net (code "109") (name "Net-(IC1A-IOB1-12{slash}GCLK0)") (class "Default")
      (node (ref "IC1") (pin "12") (pinfunction "IOB1-12/GCLK0_12") (pintype "bidirectional"))
      (node (ref "Q2") (pin "3") (pinfunction "FO_3") (pintype "output"))
    )
    (net (code "110") (name "Net-(IC1B-IOB2-62{slash}GCLK2)") (class "Default")
      (node (ref "IC1") (pin "62") (pinfunction "IOB2-62/GCLK2_62") (pintype "bidirectional"))
      (node (ref "R7") (pin "2") (pinfunction "2_2") (pintype "passive"))
    )
    (net (code "111") (name "Net-(IC1C-TCK)") (class "Default")
      (node (ref "IC1") (pin "24") (pinfunction "TCK_24") (pintype "input"))
      (node (ref "JP5") (pin "5") (pinfunction "5_5") (pintype "passive"))
      (node (ref "R9") (pin "2") (pinfunction "2_2") (pintype "passive"))
    )
    (net (code "112") (name "Net-(IC1C-TDI)") (class "Default")
      (node (ref "IC1") (pin "23") (pinfunction "TDI_23") (pintype "input"))
      (node (ref "JP5") (pin "3") (pinfunction "3_3") (pintype "passive"))
    )
    (net (code "113") (name "Net-(IC1C-TDO)") (class "Default")
      (node (ref "IC1") (pin "25") (pinfunction "TDO_25") (pintype "output"))
      (node (ref "JP5") (pin "7") (pinfunction "7_7") (pintype "passive"))
    )
    (net (code "114") (name "Net-(IC1C-TMS)") (class "Default")
      (node (ref "IC1") (pin "22") (pinfunction "TMS_22") (pintype "input"))
      (node (ref "JP5") (pin "1") (pinfunction "1_1") (pintype "passive"))
      (node (ref "R8") (pin "1") (pinfunction "1_1") (pintype "passive"))
    )
    (net (code "115") (name "Net-(IC3-IN)") (class "Default")
      (node (ref "C2") (pin "1") (pinfunction "1_1") (pintype "passive"))
      (node (ref "C5") (pin "+") (pinfunction "+_+") (pintype "passive"))
      (node (ref "D1") (pin "C") (pinfunction "C_C") (pintype "passive"))
      (node (ref "IC3") (pin "3") (pinfunction "IN_3") (pintype "input"))
    )
    (net (code "116") (name "Net-(IC3-OUT)") (class "Default")
      (node (ref "IC3") (pin "2") (pinfunction "OUT_2") (pintype "passive"))
      (node (ref "IC3") (pin "TAB") (pinfunction "OUT1_TAB") (pintype "passive"))
      (node (ref "JP1") (pin "1") (pinfunction "1_1") (pintype "passive"))
    )
    (net (code "117") (name "Net-(LED1-PadA)") (class "Default")
      (node (ref "LED1") (pin "A") (pinfunction "A_A") (pintype "passive"))
      (node (ref "R4") (pin "1") (pinfunction "1_1") (pintype "passive"))
    )
    (net (code "118") (name "Net-(LED2-PadA)") (class "Default")
      (node (ref "LED2") (pin "A") (pinfunction "A_A") (pintype "passive"))
      (node (ref "R5") (pin "1") (pinfunction "1_1") (pintype "passive"))
    )
    (net (code "119") (name "Net-(LED3-PadA)") (class "Default")
      (node (ref "LED3") (pin "A") (pinfunction "A_A") (pintype "passive"))
      (node (ref "R6") (pin "1") (pinfunction "1_1") (pintype "passive"))
    )
    (net (code "120") (name "Net-(Q1-FO)") (class "Default")
      (node (ref "Q1") (pin "3") (pinfunction "FO_3") (pintype "output"))
      (node (ref "U$1") (pin "17") (pinfunction "XTAL1_17") (pintype "bidirectional"))
    )
    (net (code "121") (name "Net-(R1-Pad1)") (class "Default")
      (node (ref "R1") (pin "1") (pinfunction "1_1") (pintype "passive"))
      (node (ref "X3") (pin "3") (pinfunction "3_3") (pintype "input"))
    )
    (net (code "122") (name "Net-(R2-Pad1)") (class "Default")
      (node (ref "R2") (pin "1") (pinfunction "1_1") (pintype "passive"))
      (node (ref "X3") (pin "2") (pinfunction "2_2") (pintype "input"))
    )
    (net (code "123") (name "Net-(U$1-(ADC0)PF0)") (class "Default")
      (node (ref "LED3") (pin "C") (pinfunction "C_C") (pintype "passive"))
      (node (ref "U$1") (pin "41") (pinfunction "(ADC0)PF0_41") (pintype "bidirectional"))
    )
    (net (code "124") (name "Net-(U$1-(ADC1)PF1)") (class "Default")
      (node (ref "LED2") (pin "C") (pinfunction "C_C") (pintype "passive"))
      (node (ref "U$1") (pin "40") (pinfunction "(ADC1)PF1_40") (pintype "bidirectional"))
    )
    (net (code "125") (name "Net-(U$1-(ADC4{slash}TCK)PF4)") (class "Default")
      (node (ref "JP7") (pin "1") (pinfunction "1_1") (pintype "passive"))
      (node (ref "U$1") (pin "39") (pinfunction "(ADC4/TCK)PF4_39") (pintype "bidirectional"))
    )
    (net (code "126") (name "Net-(U$1-(ADC5{slash}TMS)PF5)") (class "Default")
      (node (ref "JP7") (pin "5") (pinfunction "5_5") (pintype "passive"))
      (node (ref "U$1") (pin "38") (pinfunction "(ADC5/TMS)PF5_38") (pintype "bidirectional"))
    )
    (net (code "127") (name "Net-(U$1-(ADC6{slash}TDO)PF6)") (class "Default")
      (node (ref "JP7") (pin "3") (pinfunction "3_3") (pintype "passive"))
      (node (ref "U$1") (pin "37") (pinfunction "(ADC6/TDO)PF6_37") (pintype "bidirectional"))
    )
    (net (code "128") (name "Net-(U$1-(ADC7{slash}TDI)PF7)") (class "Default")
      (node (ref "JP7") (pin "9") (pinfunction "9_9") (pintype "passive"))
      (node (ref "U$1") (pin "36") (pinfunction "(ADC7/TDI)PF7_36") (pintype "bidirectional"))
    )
    (net (code "129") (name "Net-(U$1-(HWB)PE2)") (class "Default")
      (node (ref "JP8") (pin "1") (pinfunction "1_1") (pintype "passive"))
      (node (ref "R10") (pin "1") (pinfunction "1_1") (pintype "passive"))
      (node (ref "U$1") (pin "33") (pinfunction "(HWB)PE2_33") (pintype "bidirectional"))
    )
    (net (code "130") (name "Net-(U$1-D+)") (class "Default")
      (node (ref "R1") (pin "2") (pinfunction "2_2") (pintype "passive"))
      (node (ref "U$1") (pin "4") (pinfunction "D+_4") (pintype "bidirectional"))
    )
    (net (code "131") (name "Net-(U$1-D-)") (class "Default")
      (node (ref "R2") (pin "2") (pinfunction "2_2") (pintype "passive"))
      (node (ref "U$1") (pin "3") (pinfunction "D-_3") (pintype "bidirectional"))
    )
    (net (code "132") (name "V+") (class "Default")
      (node (ref "D1") (pin "A") (pinfunction "A_A") (pintype "passive"))
      (node (ref "JP4") (pin "2") (pinfunction "2_2") (pintype "passive"))
    )
    (net (code "133") (name "VCCIO") (class "Default")
      (node (ref "JP2") (pin "27") (pinfunction "27_27") (pintype "passive"))
      (node (ref "JP2") (pin "28") (pinfunction "28_28") (pintype "passive"))
      (node (ref "JP3") (pin "2") (pinfunction "2_2") (pintype "passive"))
      (node (ref "U$4") (pin "23") (pinfunction "VCCB_23") (pintype "power_in"))
      (node (ref "U$4") (pin "24") (pinfunction "VCCB_24") (pintype "power_in"))
      (node (ref "U$5") (pin "23") (pinfunction "VCCB_23") (pintype "power_in"))
      (node (ref "U$5") (pin "24") (pinfunction "VCCB_24") (pintype "power_in"))
      (node (ref "U$6") (pin "23") (pinfunction "VCCB_23") (pintype "power_in"))
      (node (ref "U$6") (pin "24") (pinfunction "VCCB_24") (pintype "power_in"))
    )
    (net (code "134") (name "unconnected-(IC1A-IOB1-43{slash}DEV_OE-Pad43)") (class "Default")
      (node (ref "IC1") (pin "43") (pinfunction "IOB1-43/DEV_OE_43") (pintype "bidirectional"))
    )
    (net (code "135") (name "unconnected-(IC1A-IOB1-44{slash}DEV_CLR-Pad44)") (class "Default")
      (node (ref "IC1") (pin "44") (pinfunction "IOB1-44/DEV_CLR_44") (pintype "bidirectional"))
    )
    (net (code "136") (name "unconnected-(IC1B-IOB2-64{slash}GCLK3-Pad64)") (class "Default")
      (node (ref "IC1") (pin "64") (pinfunction "IOB2-64/GCLK3_64") (pintype "bidirectional"))
    )
    (net (code "137") (name "unconnected-(JP7-Pad7)") (class "Default")
      (node (ref "JP7") (pin "7") (pinfunction "7_7") (pintype "passive"))
    )
    (net (code "138") (name "unconnected-(JP7-Pad8)") (class "Default")
      (node (ref "JP7") (pin "8") (pinfunction "8_8") (pintype "passive"))
    )
    (net (code "139") (name "unconnected-(U$1-(INT6{slash}AIN0)PE6-Pad1)") (class "Default")
      (node (ref "U$1") (pin "1") (pinfunction "(INT6/AIN0)PE6_1") (pintype "bidirectional"))
    )
    (net (code "140") (name "unconnected-(U$1-(OC3A{slash}OC4A)PC6-Pad31)") (class "Default")
      (node (ref "U$1") (pin "31") (pinfunction "(OC3A/OC4A)PC6_31") (pintype "bidirectional"))
    )
    (net (code "141") (name "unconnected-(U$1-(PCINT5{slash}OC1A{slash}OC4B{slash}ADC12)PB5-Pad29)") (class "Default")
      (node (ref "U$1") (pin "29") (pinfunction "(PCINT5/OC1A/OC4B/ADC12)PB5_29") (pintype "bidirectional"))
    )
    (net (code "142") (name "unconnected-(U$1-(PCINT6{slash}OC1B{slash}OC4B{slash}ADC13)PB6-Pad30)") (class "Default")
      (node (ref "U$1") (pin "30") (pinfunction "(PCINT6/OC1B/OC4B/ADC13)PB6_30") (pintype "bidirectional"))
    )
    (net (code "143") (name "unconnected-(U$1-(SS{slash}PCINT0)PB0-Pad8)") (class "Default")
      (node (ref "U$1") (pin "8") (pinfunction "(SS/PCINT0)PB0_8") (pintype "bidirectional"))
    )
    (net (code "144") (name "unconnected-(U$1-AREF-Pad42)") (class "Default")
      (node (ref "U$1") (pin "42") (pinfunction "AREF_42") (pintype "bidirectional"))
    )
    (net (code "145") (name "unconnected-(U$1-UVCC-Pad2)") (class "Default")
      (node (ref "U$1") (pin "2") (pinfunction "UVCC_2") (pintype "bidirectional"))
    )
    (net (code "146") (name "unconnected-(U$1-XTAL2-Pad16)") (class "Default")
      (node (ref "U$1") (pin "16") (pinfunction "XTAL2_16") (pintype "bidirectional"))
    )
    (net (code "147") (name "unconnected-(U$2-NC-Pad28)") (class "Default")
      (node (ref "U$2") (pin "28") (pinfunction "NC_28") (pintype "no_connect"))
    )
    (net (code "148") (name "unconnected-(U$3-NC-Pad28)") (class "Default")
      (node (ref "U$3") (pin "28") (pinfunction "NC_28") (pintype "no_connect"))
    )
    (net (code "149") (name "unconnected-(X3-Pad5)") (class "Default")
      (node (ref "X3") (pin "5") (pinfunction "5_5") (pintype "input"))
    )
  )
)
